# HG8M_breakout.net
KiCad netlist of a schematic drawn in EAGLE
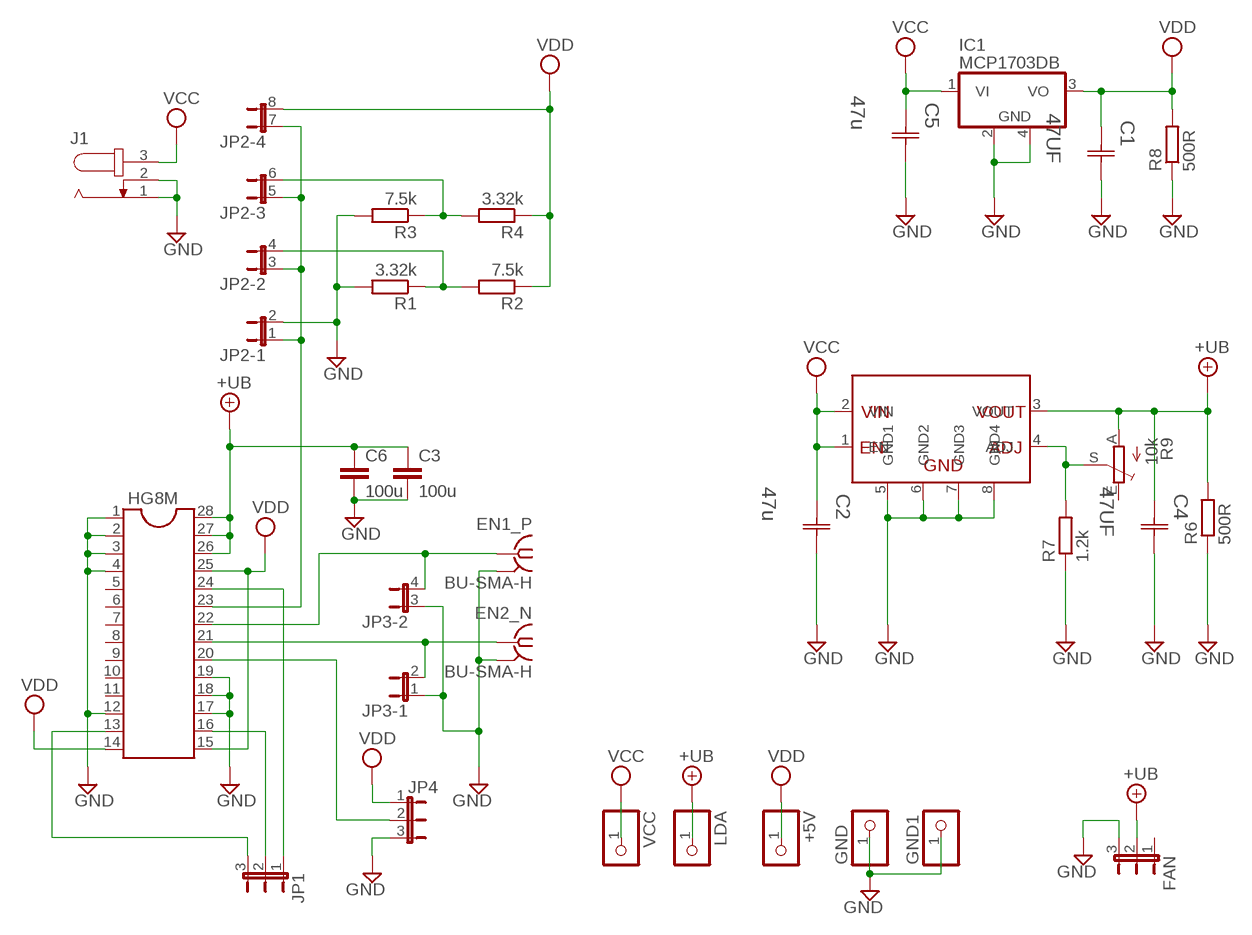
[diagram p0: schematic, sheet 1]

(export (version "E")
  (design (tool "Eeschema 10.0.6"))
  (components
    (comp (ref "+5V")
      (value "PINHD-1X1")
      (footprint "eagle-import:1X01")
      (libsource (lib "eagle-import") (part "PINHD-1X1"))
    )
    (comp (ref "C1")
      (value "47UF")
      (footprint "eagle-import:CAPCP6032X280N")
      (fields (field (name "MPN") "TPSC476M010R0350"))
      (libsource (lib "eagle-import") (part "TPSC476M010R0350"))
    )
    (comp (ref "C2")
      (value "47u")
      (footprint "eagle-import:CAPC3225X94N")
      (fields (field (name "MPN") "12101A471JAT2A") (field (name "TOLERANCE") "±5%"))
      (libsource (lib "eagle-import") (part "12101A471JAT2A"))
    )
    (comp (ref "C3")
      (value "100u")
      (footprint "eagle-import:C1210")
      (libsource (lib "eagle-import") (part "C-EUC1210"))
    )
    (comp (ref "C4")
      (value "47UF")
      (footprint "eagle-import:CAPCP6032X280N")
      (fields (field (name "MPN") "TPSC476M010R0350"))
      (libsource (lib "eagle-import") (part "TPSC476M010R0350"))
    )
    (comp (ref "C5")
      (value "47u")
      (footprint "eagle-import:CAPC3225X94N")
      (fields (field (name "MPN") "12101A471JAT2A") (field (name "TOLERANCE") "±5%"))
      (libsource (lib "eagle-import") (part "12101A471JAT2A"))
    )
    (comp (ref "C6")
      (value "100u")
      (footprint "eagle-import:C1210")
      (libsource (lib "eagle-import") (part "C-EUC1210"))
    )
    (comp (ref "EN1_P")
      (value "BU-SMA-H")
      (footprint "eagle-import:BU-SMA-H")
      (libsource (lib "eagle-import") (part "BU-SMA-H"))
    )
    (comp (ref "EN2_N")
      (value "BU-SMA-H")
      (footprint "eagle-import:BU-SMA-H")
      (libsource (lib "eagle-import") (part "BU-SMA-H"))
    )
    (comp (ref "FAN")
      (value "JP2E")
      (footprint "eagle-import:JP2")
      (libsource (lib "eagle-import") (part "JP2E"))
    )
    (comp (ref "GND")
      (value "PINHD-1X1")
      (footprint "eagle-import:1X01")
      (libsource (lib "eagle-import") (part "PINHD-1X1"))
    )
    (comp (ref "GND1")
      (value "PINHD-1X1")
      (footprint "eagle-import:1X01")
      (libsource (lib "eagle-import") (part "PINHD-1X1"))
    )
    (comp (ref "HG8M")
      (value "DIL28")
      (footprint "eagle-import:DIL28-6")
      (libsource (lib "eagle-import") (part "DIL28"))
    )
    (comp (ref "IC1")
      (value "MCP1703DB")
      (footprint "eagle-import:SOT223")
      (libsource (lib "eagle-import") (part "MCP1703DB"))
    )
    (comp (ref "J1")
      (value "JACK-PLUG1")
      (footprint "eagle-import:SPC4078")
      (libsource (lib "eagle-import") (part "JACK-PLUG1"))
    )
    (comp (ref "JP1")
      (value "JP2E")
      (footprint "eagle-import:JP2")
      (libsource (lib "eagle-import") (part "JP2E"))
    )
    (comp (ref "JP2")
      (value "JP4QE")
      (footprint "eagle-import:JP4Q")
      (libsource (lib "eagle-import") (part "JP4QE"))
    )
    (comp (ref "JP3")
      (value "JP2QE")
      (footprint "eagle-import:JP2Q")
      (libsource (lib "eagle-import") (part "JP2QE"))
    )
    (comp (ref "JP4")
      (value "JP2E")
      (footprint "eagle-import:JP2")
      (libsource (lib "eagle-import") (part "JP2E"))
    )
    (comp (ref "LDA")
      (value "PINHD-1X1")
      (footprint "eagle-import:1X01")
      (libsource (lib "eagle-import") (part "PINHD-1X1"))
    )
    (comp (ref "R1")
      (value "3.32k")
      (footprint "eagle-import:R0805")
      (libsource (lib "eagle-import") (part "R-EU_R0805"))
    )
    (comp (ref "R2")
      (value "7.5k")
      (footprint "eagle-import:R0805")
      (libsource (lib "eagle-import") (part "R-EU_R0805"))
    )
    (comp (ref "R3")
      (value "7.5k")
      (footprint "eagle-import:R0805")
      (libsource (lib "eagle-import") (part "R-EU_R0805"))
    )
    (comp (ref "R4")
      (value "3.32k")
      (footprint "eagle-import:R0805")
      (libsource (lib "eagle-import") (part "R-EU_R0805"))
    )
    (comp (ref "R6")
      (value "500R")
      (footprint "eagle-import:R0805")
      (libsource (lib "eagle-import") (part "R-EU_R0805"))
    )
    (comp (ref "R7")
      (value "1.2k")
      (footprint "eagle-import:R0805")
      (libsource (lib "eagle-import") (part "R-EU_R0805"))
    )
    (comp (ref "R8")
      (value "500R")
      (footprint "eagle-import:R0805")
      (libsource (lib "eagle-import") (part "R-EU_R0805"))
    )
    (comp (ref "R9")
      (value "10k")
      (footprint "eagle-import:B64W")
      (libsource (lib "eagle-import") (part "TRIM_EU-B64W"))
    )
    (comp (ref "U$4")
      (value "MIC39102")
      (footprint "eagle-import:SOIC8")
      (libsource (lib "eagle-import") (part "MIC39102"))
    )
    (comp (ref "VCC")
      (value "PINHD-1X1")
      (footprint "eagle-import:1X01")
      (libsource (lib "eagle-import") (part "PINHD-1X1"))
    )
  )
  (nets
    (net (code "1") (name "+UB") (class "Default")
      (node (ref "C3") (pin "1") (pinfunction "1_1") (pintype "passive"))
      (node (ref "C4") (pin "1") (pinfunction "C1_1") (pintype "passive"))
      (node (ref "C6") (pin "1") (pinfunction "1_1") (pintype "passive"))
      (node (ref "FAN") (pin "2") (pinfunction "2_2") (pintype "passive"))
      (node (ref "HG8M") (pin "26") (pinfunction "26_26") (pintype "passive"))
      (node (ref "HG8M") (pin "27") (pinfunction "27_27") (pintype "passive"))
      (node (ref "HG8M") (pin "28") (pinfunction "28_28") (pintype "passive"))
      (node (ref "LDA") (pin "1") (pinfunction "1_1") (pintype "passive"))
      (node (ref "R6") (pin "2") (pinfunction "2_2") (pintype "passive"))
      (node (ref "R9") (pin "A") (pinfunction "A_A") (pintype "passive"))
      (node (ref "U$4") (pin "3") (pinfunction "VOUT_3") (pintype "bidirectional"))
    )
    (net (code "2") (name "GND") (class "Default")
      (node (ref "C1") (pin "2") (pinfunction "C2_2") (pintype "passive"))
      (node (ref "C2") (pin "2") (pinfunction "C2_2") (pintype "passive"))
      (node (ref "C3") (pin "2") (pinfunction "2_2") (pintype "passive"))
      (node (ref "C4") (pin "2") (pinfunction "C2_2") (pintype "passive"))
      (node (ref "C5") (pin "2") (pinfunction "C2_2") (pintype "passive"))
      (node (ref "C6") (pin "2") (pinfunction "2_2") (pintype "passive"))
      (node (ref "EN1_P") (pin "2") (pinfunction "2_2") (pintype "passive"))
      (node (ref "EN1_P") (pin "3") (pinfunction "2_3") (pintype "passive"))
      (node (ref "EN1_P") (pin "4") (pinfunction "2_4") (pintype "passive"))
      (node (ref "EN1_P") (pin "5") (pinfunction "2_5") (pintype "passive"))
      (node (ref "EN2_N") (pin "2") (pinfunction "2_2") (pintype "passive"))
      (node (ref "EN2_N") (pin "3") (pinfunction "2_3") (pintype "passive"))
      (node (ref "EN2_N") (pin "4") (pinfunction "2_4") (pintype "passive"))
      (node (ref "EN2_N") (pin "5") (pinfunction "2_5") (pintype "passive"))
      (node (ref "FAN") (pin "3") (pinfunction "3_3") (pintype "passive"))
      (node (ref "GND") (pin "1") (pinfunction "1_1") (pintype "passive"))
      (node (ref "GND1") (pin "1") (pinfunction "1_1") (pintype "passive"))
      (node (ref "HG8M") (pin "1") (pinfunction "1_1") (pintype "passive"))
      (node (ref "HG8M") (pin "12") (pinfunction "12_12") (pintype "passive"))
      (node (ref "HG8M") (pin "17") (pinfunction "17_17") (pintype "passive"))
      (node (ref "HG8M") (pin "18") (pinfunction "18_18") (pintype "passive"))
      (node (ref "HG8M") (pin "19") (pinfunction "19_19") (pintype "passive"))
      (node (ref "HG8M") (pin "2") (pinfunction "2_2") (pintype "passive"))
      (node (ref "HG8M") (pin "3") (pinfunction "3_3") (pintype "passive"))
      (node (ref "HG8M") (pin "4") (pinfunction "4_4") (pintype "passive"))
      (node (ref "IC1") (pin "2") (pinfunction "GND_2") (pintype "passive"))
      (node (ref "IC1") (pin "4") (pinfunction "TAP_4") (pintype "passive"))
      (node (ref "J1") (pin "1") (pinfunction "1_1") (pintype "passive"))
      (node (ref "J1") (pin "2") (pinfunction "2_2") (pintype "passive"))
      (node (ref "JP2") (pin "2") (pinfunction "2_2") (pintype "passive"))
      (node (ref "JP3") (pin "1") (pinfunction "1_1") (pintype "passive"))
      (node (ref "JP3") (pin "3") (pinfunction "1_3") (pintype "passive"))
      (node (ref "JP4") (pin "3") (pinfunction "3_3") (pintype "passive"))
      (node (ref "R1") (pin "2") (pinfunction "2_2") (pintype "passive"))
      (node (ref "R3") (pin "2") (pinfunction "2_2") (pintype "passive"))
      (node (ref "R6") (pin "1") (pinfunction "1_1") (pintype "passive"))
      (node (ref "R7") (pin "1") (pinfunction "1_1") (pintype "passive"))
      (node (ref "R8") (pin "1") (pinfunction "1_1") (pintype "passive"))
      (node (ref "U$4") (pin "5") (pinfunction "GND1_5") (pintype "bidirectional"))
      (node (ref "U$4") (pin "6") (pinfunction "GND2_6") (pintype "bidirectional"))
      (node (ref "U$4") (pin "7") (pinfunction "GND3_7") (pintype "bidirectional"))
      (node (ref "U$4") (pin "8") (pinfunction "GND4_8") (pintype "bidirectional"))
    )
    (net (code "3") (name "Net-(EN2_N-Pad1)") (class "Default")
      (node (ref "EN2_N") (pin "1") (pinfunction "1_1") (pintype "passive"))
      (node (ref "HG8M") (pin "21") (pinfunction "21_21") (pintype "passive"))
      (node (ref "JP3") (pin "2") (pinfunction "2_2") (pintype "passive"))
    )
    (net (code "4") (name "Net-(HG8M-Pad13)") (class "Default")
      (node (ref "HG8M") (pin "13") (pinfunction "13_13") (pintype "passive"))
      (node (ref "JP1") (pin "3") (pinfunction "3_3") (pintype "passive"))
    )
    (net (code "5") (name "Net-(HG8M-Pad16)") (class "Default")
      (node (ref "HG8M") (pin "16") (pinfunction "16_16") (pintype "passive"))
      (node (ref "JP1") (pin "2") (pinfunction "2_2") (pintype "passive"))
    )
    (net (code "6") (name "Net-(HG8M-Pad20)") (class "Default")
      (node (ref "HG8M") (pin "20") (pinfunction "20_20") (pintype "passive"))
      (node (ref "JP4") (pin "2") (pinfunction "2_2") (pintype "passive"))
    )
    (net (code "7") (name "Net-(HG8M-Pad24)") (class "Default")
      (node (ref "HG8M") (pin "24") (pinfunction "24_24") (pintype "passive"))
      (node (ref "JP1") (pin "1") (pinfunction "1_1") (pintype "passive"))
    )
    (net (code "8") (name "Net-(JP2B-1)") (class "Default")
      (node (ref "HG8M") (pin "23") (pinfunction "23_23") (pintype "passive"))
      (node (ref "JP2") (pin "1") (pinfunction "1_1") (pintype "passive"))
      (node (ref "JP2") (pin "3") (pinfunction "1_3") (pintype "passive"))
      (node (ref "JP2") (pin "5") (pinfunction "1_5") (pintype "passive"))
      (node (ref "JP2") (pin "7") (pinfunction "1_7") (pintype "passive"))
    )
    (net (code "9") (name "Net-(JP2B-2)") (class "Default")
      (node (ref "JP2") (pin "4") (pinfunction "2_4") (pintype "passive"))
      (node (ref "R1") (pin "1") (pinfunction "1_1") (pintype "passive"))
      (node (ref "R2") (pin "2") (pinfunction "2_2") (pintype "passive"))
    )
    (net (code "10") (name "Net-(JP2C-2)") (class "Default")
      (node (ref "JP2") (pin "6") (pinfunction "2_6") (pintype "passive"))
      (node (ref "R3") (pin "1") (pinfunction "1_1") (pintype "passive"))
      (node (ref "R4") (pin "2") (pinfunction "2_2") (pintype "passive"))
    )
    (net (code "11") (name "Net-(JP3B-2)") (class "Default")
      (node (ref "EN1_P") (pin "1") (pinfunction "1_1") (pintype "passive"))
      (node (ref "HG8M") (pin "22") (pinfunction "22_22") (pintype "passive"))
      (node (ref "JP3") (pin "4") (pinfunction "2_4") (pintype "passive"))
    )
    (net (code "12") (name "Net-(U$4-ADJ)") (class "Default")
      (node (ref "R7") (pin "2") (pinfunction "2_2") (pintype "passive"))
      (node (ref "R9") (pin "S") (pinfunction "S_S") (pintype "passive"))
      (node (ref "U$4") (pin "4") (pinfunction "ADJ_4") (pintype "bidirectional"))
    )
    (net (code "13") (name "VCC") (class "Default")
      (node (ref "C2") (pin "1") (pinfunction "C1_1") (pintype "passive"))
      (node (ref "C5") (pin "1") (pinfunction "C1_1") (pintype "passive"))
      (node (ref "IC1") (pin "1") (pinfunction "VI_1") (pintype "input"))
      (node (ref "J1") (pin "3") (pinfunction "3_3") (pintype "passive"))
      (node (ref "U$4") (pin "1") (pinfunction "EN_1") (pintype "bidirectional"))
      (node (ref "U$4") (pin "2") (pinfunction "VIN_2") (pintype "bidirectional"))
      (node (ref "VCC") (pin "1") (pinfunction "1_1") (pintype "passive"))
    )
    (net (code "14") (name "VDD") (class "Default")
      (node (ref "+5V") (pin "1") (pinfunction "1_1") (pintype "passive"))
      (node (ref "C1") (pin "1") (pinfunction "C1_1") (pintype "passive"))
      (node (ref "HG8M") (pin "14") (pinfunction "14_14") (pintype "passive"))
      (node (ref "HG8M") (pin "15") (pinfunction "15_15") (pintype "passive"))
      (node (ref "HG8M") (pin "25") (pinfunction "25_25") (pintype "passive"))
      (node (ref "IC1") (pin "3") (pinfunction "VO_3") (pintype "passive"))
      (node (ref "JP2") (pin "8") (pinfunction "2_8") (pintype "passive"))
      (node (ref "JP4") (pin "1") (pinfunction "1_1") (pintype "passive"))
      (node (ref "R2") (pin "1") (pinfunction "1_1") (pintype "passive"))
      (node (ref "R4") (pin "1") (pinfunction "1_1") (pintype "passive"))
      (node (ref "R8") (pin "2") (pinfunction "2_2") (pintype "passive"))
    )
    (net (code "15") (name "unconnected-(FAN-Pad1)") (class "Default")
      (node (ref "FAN") (pin "1") (pinfunction "1_1") (pintype "passive"))
    )
    (net (code "16") (name "unconnected-(HG8M-Pad5)") (class "Default")
      (node (ref "HG8M") (pin "5") (pinfunction "5_5") (pintype "passive"))
    )
    (net (code "17") (name "unconnected-(HG8M-Pad6)") (class "Default")
      (node (ref "HG8M") (pin "6") (pinfunction "6_6") (pintype "passive"))
    )
    (net (code "18") (name "unconnected-(HG8M-Pad7)") (class "Default")
      (node (ref "HG8M") (pin "7") (pinfunction "7_7") (pintype "passive"))
    )
    (net (code "19") (name "unconnected-(HG8M-Pad8)") (class "Default")
      (node (ref "HG8M") (pin "8") (pinfunction "8_8") (pintype "passive"))
    )
    (net (code "20") (name "unconnected-(HG8M-Pad9)") (class "Default")
      (node (ref "HG8M") (pin "9") (pinfunction "9_9") (pintype "passive"))
    )
    (net (code "21") (name "unconnected-(HG8M-Pad10)") (class "Default")
      (node (ref "HG8M") (pin "10") (pinfunction "10_10") (pintype "passive"))
    )
    (net (code "22") (name "unconnected-(HG8M-Pad11)") (class "Default")
      (node (ref "HG8M") (pin "11") (pinfunction "11_11") (pintype "passive"))
    )
    (net (code "23") (name "unconnected-(R9-PadE)") (class "Default")
      (node (ref "R9") (pin "E") (pinfunction "E_E") (pintype "passive"))
    )
  )
)
